# schematic-sac-xa-4s.net
KiCad netlist of a schematic drawn in Altium Designer
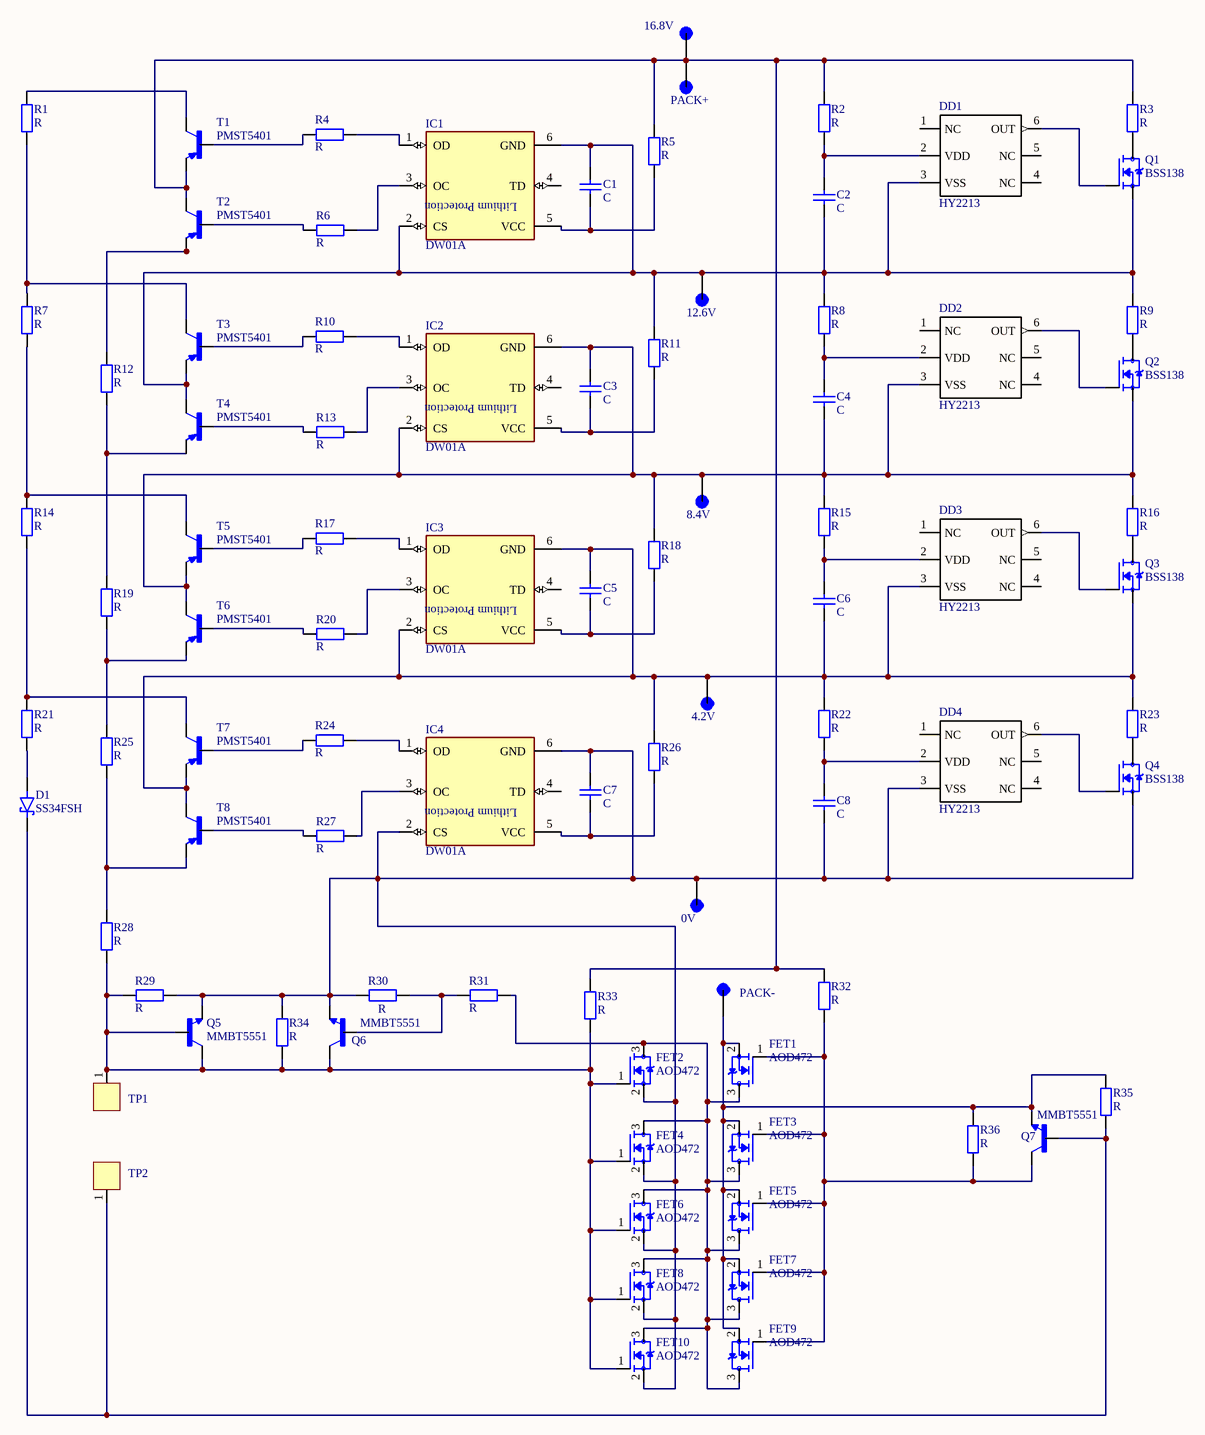
[diagram p0: schematic-sac-xa-4s.schdoc]

(export (version "E")
  (design (tool "Eeschema 10.0.6"))
  (components
    (comp (ref "0V")
      (value "5003")
      (footprint "KEYSTONE_5003")
      (fields (field (name "MF") "{'manufacturer': u'Keystone Electronics'}"))
      (libsource (lib "test pond") (part "5003"))
    )
    (comp (ref "4.2V")
      (value "5003")
      (footprint "KEYSTONE_5003")
      (fields (field (name "MF") "{'manufacturer': u'Keystone Electronics'}"))
      (libsource (lib "test pond") (part "5003"))
    )
    (comp (ref "8.4V")
      (value "5003")
      (footprint "KEYSTONE_5003")
      (fields (field (name "MF") "{'manufacturer': u'Keystone Electronics'}"))
      (libsource (lib "test pond") (part "5003"))
    )
    (comp (ref "12.6V")
      (value "5003")
      (footprint "KEYSTONE_5003")
      (fields (field (name "MF") "{'manufacturer': u'Keystone Electronics'}"))
      (libsource (lib "test pond") (part "5003"))
    )
    (comp (ref "16.8V")
      (value "5003")
      (footprint "KEYSTONE_5003")
      (fields (field (name "MF") "{'manufacturer': u'Keystone Electronics'}"))
      (libsource (lib "test pond") (part "5003"))
    )
    (comp (ref "C1")
      (value "C")
      (footprint "tu 0603")
      (description "Dán")
      (libsource (lib "Altium_Lib_by_KhueNguyenCreator") (part "Tu 0603 105 50V 10%"))
    )
    (comp (ref "C2")
      (value "C")
      (footprint "tu 0603")
      (description "Dán")
      (libsource (lib "Altium_Lib_by_KhueNguyenCreator") (part "Tu 0603 105 50V 10%"))
    )
    (comp (ref "C3")
      (value "C")
      (footprint "tu 0603")
      (description "Dán")
      (libsource (lib "Altium_Lib_by_KhueNguyenCreator") (part "Tu 0603 105 50V 10%"))
    )
    (comp (ref "C4")
      (value "C")
      (footprint "tu 0603")
      (description "Dán")
      (libsource (lib "Altium_Lib_by_KhueNguyenCreator") (part "Tu 0603 105 50V 10%"))
    )
    (comp (ref "C5")
      (value "C")
      (footprint "tu 0603")
      (description "Dán")
      (libsource (lib "Altium_Lib_by_KhueNguyenCreator") (part "Tu 0603 105 50V 10%"))
    )
    (comp (ref "C6")
      (value "C")
      (footprint "tu 0603")
      (description "Dán")
      (libsource (lib "Altium_Lib_by_KhueNguyenCreator") (part "Tu 0603 105 50V 10%"))
    )
    (comp (ref "C7")
      (value "C")
      (footprint "tu 0603")
      (description "Dán")
      (libsource (lib "Altium_Lib_by_KhueNguyenCreator") (part "Tu 0603 105 50V 10%"))
    )
    (comp (ref "C8")
      (value "C")
      (footprint "tu 0603")
      (description "Dán")
      (libsource (lib "Altium_Lib_by_KhueNguyenCreator") (part "Tu 0603 105 50V 10%"))
    )
    (comp (ref "D1")
      (value "SS34FSH")
      (footprint "SODFL4725X110N")
      (description "3A, 40V, Schottky Rectifier")
      (fields (field (name "MF") "Taiwan Semiconductor"))
      (libsource (lib "SS34FSH") (part "SS34FSH"))
    )
    (comp (ref "DD1")
      (value "HY2213")
      (footprint "SOT23-6")
      (description "1 Cell Li-ion/Polymer Battery Charge Balance IC")
      (libsource (lib "HY2213-BB3A") (part "HY2213"))
    )
    (comp (ref "DD2")
      (value "HY2213")
      (footprint "SOT23-6")
      (description "1 Cell Li-ion/Polymer Battery Charge Balance IC")
      (libsource (lib "HY2213-BB3A") (part "HY2213"))
    )
    (comp (ref "DD3")
      (value "HY2213")
      (footprint "SOT23-6")
      (description "1 Cell Li-ion/Polymer Battery Charge Balance IC")
      (libsource (lib "HY2213-BB3A") (part "HY2213"))
    )
    (comp (ref "DD4")
      (value "HY2213")
      (footprint "SOT23-6")
      (description "1 Cell Li-ion/Polymer Battery Charge Balance IC")
      (libsource (lib "HY2213-BB3A") (part "HY2213"))
    )
    (comp (ref "FET1")
      (value "AOD472")
      (footprint "PCBComponent_1")
      (libsource (lib "Mosfet AOD472") (part "AOD472"))
    )
    (comp (ref "FET2")
      (value "AOD472")
      (footprint "PCBComponent_1")
      (libsource (lib "Mosfet AOD472") (part "AOD472"))
    )
    (comp (ref "FET3")
      (value "AOD472")
      (footprint "PCBComponent_1")
      (libsource (lib "Mosfet AOD472") (part "AOD472"))
    )
    (comp (ref "FET4")
      (value "AOD472")
      (footprint "PCBComponent_1")
      (libsource (lib "Mosfet AOD472") (part "AOD472"))
    )
    (comp (ref "FET5")
      (value "AOD472")
      (footprint "PCBComponent_1")
      (libsource (lib "Mosfet AOD472") (part "AOD472"))
    )
    (comp (ref "FET6")
      (value "AOD472")
      (footprint "PCBComponent_1")
      (libsource (lib "Mosfet AOD472") (part "AOD472"))
    )
    (comp (ref "FET7")
      (value "AOD472")
      (footprint "PCBComponent_1")
      (libsource (lib "Mosfet AOD472") (part "AOD472"))
    )
    (comp (ref "FET8")
      (value "AOD472")
      (footprint "PCBComponent_1")
      (libsource (lib "Mosfet AOD472") (part "AOD472"))
    )
    (comp (ref "FET9")
      (value "AOD472")
      (footprint "PCBComponent_1")
      (libsource (lib "Mosfet AOD472") (part "AOD472"))
    )
    (comp (ref "FET10")
      (value "AOD472")
      (footprint "PCBComponent_1")
      (libsource (lib "Mosfet AOD472") (part "AOD472"))
    )
    (comp (ref "IC1")
      (value "DW01A")
      (footprint "SOT23-6")
      (description "One Cell Lithium-ion/Polymer Battery Protection IC")
      (fields (field (name "MF") "Fortune Semiconductor"))
      (libsource (lib "DW01A") (part "DW01A"))
    )
    (comp (ref "IC2")
      (value "DW01A")
      (footprint "SOT23-6")
      (description "One Cell Lithium-ion/Polymer Battery Protection IC")
      (fields (field (name "MF") "Fortune Semiconductor"))
      (libsource (lib "DW01A") (part "DW01A"))
    )
    (comp (ref "IC3")
      (value "DW01A")
      (footprint "SOT23-6")
      (description "One Cell Lithium-ion/Polymer Battery Protection IC")
      (fields (field (name "MF") "Fortune Semiconductor"))
      (libsource (lib "DW01A") (part "DW01A"))
    )
    (comp (ref "IC4")
      (value "DW01A")
      (footprint "SOT23-6")
      (description "One Cell Lithium-ion/Polymer Battery Protection IC")
      (fields (field (name "MF") "Fortune Semiconductor"))
      (libsource (lib "DW01A") (part "DW01A"))
    )
    (comp (ref "PACK+")
      (value "5003")
      (footprint "KEYSTONE_5003")
      (fields (field (name "MF") "{'manufacturer': u'Keystone Electronics'}"))
      (libsource (lib "test pond") (part "5003"))
    )
    (comp (ref "PACK-")
      (value "5003")
      (footprint "KEYSTONE_5003")
      (fields (field (name "MF") "{'manufacturer': u'Keystone Electronics'}"))
      (libsource (lib "test pond") (part "5003"))
    )
    (comp (ref "Q1")
      (value "BSS138")
      (footprint "SOT95P240X111-3N")
      (description "N-Channel 50V 220mA (Ta) 360mW (Ta) Surface Mount SOT-23-3")
      (fields (field (name "MF") "ON Semiconductor"))
      (libsource (lib "BSS138") (part "BSS138"))
    )
    (comp (ref "Q2")
      (value "BSS138")
      (footprint "SOT95P240X111-3N")
      (description "N-Channel 50V 220mA (Ta) 360mW (Ta) Surface Mount SOT-23-3")
      (fields (field (name "MF") "ON Semiconductor"))
      (libsource (lib "BSS138") (part "BSS138"))
    )
    (comp (ref "Q3")
      (value "BSS138")
      (footprint "SOT95P240X111-3N")
      (description "N-Channel 50V 220mA (Ta) 360mW (Ta) Surface Mount SOT-23-3")
      (fields (field (name "MF") "ON Semiconductor"))
      (libsource (lib "BSS138") (part "BSS138"))
    )
    (comp (ref "Q4")
      (value "BSS138")
      (footprint "SOT95P240X111-3N")
      (description "N-Channel 50V 220mA (Ta) 360mW (Ta) Surface Mount SOT-23-3")
      (fields (field (name "MF") "ON Semiconductor"))
      (libsource (lib "BSS138") (part "BSS138"))
    )
    (comp (ref "Q5")
      (value "MMBT5551")
      (footprint "SOT23-3")
      (description "Bipolar _BJT_ Transistor NPN 160V 600mA 225mW Surface Mount SOT-23-3 _TO-236_")
      (fields (field (name "MF") "ON Semiconductor"))
      (libsource (lib "") (part "MMBT5551_1"))
    )
    (comp (ref "Q6")
      (value "MMBT5551")
      (footprint "SOT23-3")
      (description "Bipolar _BJT_ Transistor NPN 160V 600mA 225mW Surface Mount SOT-23-3 _TO-236_")
      (fields (field (name "MF") "ON Semiconductor"))
      (libsource (lib "MMBT5551") (part "MMBT5551"))
    )
    (comp (ref "Q7")
      (value "MMBT5551")
      (footprint "SOT23-3")
      (description "Bipolar _BJT_ Transistor NPN 160V 600mA 225mW Surface Mount SOT-23-3 _TO-236_")
      (fields (field (name "MF") "ON Semiconductor"))
      (libsource (lib "MMBT5551") (part "MMBT5551"))
    )
    (comp (ref "R1")
      (value "R")
      (footprint "tro smd 0603")
      (description "Dán")
      (libsource (lib "Altium_Lib_by_KhueNguyenCreator") (part "Tro 0603 5% 100R"))
    )
    (comp (ref "R2")
      (value "R")
      (footprint "tro smd 0603")
      (description "Dán")
      (libsource (lib "Altium_Lib_by_KhueNguyenCreator") (part "Tro 0603 5% 100R"))
    )
    (comp (ref "R3")
      (value "R")
      (footprint "tro smd 0603")
      (description "Dán")
      (libsource (lib "Altium_Lib_by_KhueNguyenCreator") (part "Tro 0603 5% 100R"))
    )
    (comp (ref "R4")
      (value "R")
      (footprint "tro smd 0603")
      (description "Dán")
      (libsource (lib "Altium_Lib_by_KhueNguyenCreator") (part "Tro 0603 5% 100R"))
    )
    (comp (ref "R5")
      (value "R")
      (footprint "tro smd 0603")
      (description "Dán")
      (libsource (lib "Altium_Lib_by_KhueNguyenCreator") (part "Tro 0603 5% 100R"))
    )
    (comp (ref "R6")
      (value "R")
      (footprint "tro smd 0603")
      (description "Dán")
      (libsource (lib "Altium_Lib_by_KhueNguyenCreator") (part "Tro 0603 5% 100R"))
    )
    (comp (ref "R7")
      (value "R")
      (footprint "tro smd 0603")
      (description "Dán")
      (libsource (lib "Altium_Lib_by_KhueNguyenCreator") (part "Tro 0603 5% 100R"))
    )
    (comp (ref "R8")
      (value "R")
      (footprint "tro smd 0603")
      (description "Dán")
      (libsource (lib "Altium_Lib_by_KhueNguyenCreator") (part "Tro 0603 5% 100R"))
    )
    (comp (ref "R9")
      (value "R")
      (footprint "tro smd 0603")
      (description "Dán")
      (libsource (lib "Altium_Lib_by_KhueNguyenCreator") (part "Tro 0603 5% 100R"))
    )
    (comp (ref "R10")
      (value "R")
      (footprint "tro smd 0603")
      (description "Dán")
      (libsource (lib "Altium_Lib_by_KhueNguyenCreator") (part "Tro 0603 5% 100R"))
    )
    (comp (ref "R11")
      (value "R")
      (footprint "tro smd 0603")
      (description "Dán")
      (libsource (lib "Altium_Lib_by_KhueNguyenCreator") (part "Tro 0603 5% 100R"))
    )
    (comp (ref "R12")
      (value "R")
      (footprint "tro smd 0603")
      (description "Dán")
      (libsource (lib "Altium_Lib_by_KhueNguyenCreator") (part "Tro 0603 5% 100R"))
    )
    (comp (ref "R13")
      (value "R")
      (footprint "tro smd 0603")
      (description "Dán")
      (libsource (lib "Altium_Lib_by_KhueNguyenCreator") (part "Tro 0603 5% 100R"))
    )
    (comp (ref "R14")
      (value "R")
      (footprint "tro smd 0603")
      (description "Dán")
      (libsource (lib "Altium_Lib_by_KhueNguyenCreator") (part "Tro 0603 5% 100R"))
    )
    (comp (ref "R15")
      (value "R")
      (footprint "tro smd 0603")
      (description "Dán")
      (libsource (lib "Altium_Lib_by_KhueNguyenCreator") (part "Tro 0603 5% 100R"))
    )
    (comp (ref "R16")
      (value "R")
      (footprint "tro smd 0603")
      (description "Dán")
      (libsource (lib "Altium_Lib_by_KhueNguyenCreator") (part "Tro 0603 5% 100R"))
    )
    (comp (ref "R17")
      (value "R")
      (footprint "tro smd 0603")
      (description "Dán")
      (libsource (lib "Altium_Lib_by_KhueNguyenCreator") (part "Tro 0603 5% 100R"))
    )
    (comp (ref "R18")
      (value "R")
      (footprint "tro smd 0603")
      (description "Dán")
      (libsource (lib "Altium_Lib_by_KhueNguyenCreator") (part "Tro 0603 5% 100R"))
    )
    (comp (ref "R19")
      (value "R")
      (footprint "tro smd 0603")
      (description "Dán")
      (libsource (lib "Altium_Lib_by_KhueNguyenCreator") (part "Tro 0603 5% 100R"))
    )
    (comp (ref "R20")
      (value "R")
      (footprint "tro smd 0603")
      (description "Dán")
      (libsource (lib "Altium_Lib_by_KhueNguyenCreator") (part "Tro 0603 5% 100R"))
    )
    (comp (ref "R21")
      (value "R")
      (footprint "tro smd 0603")
      (description "Dán")
      (libsource (lib "Altium_Lib_by_KhueNguyenCreator") (part "Tro 0603 5% 100R"))
    )
    (comp (ref "R22")
      (value "R")
      (footprint "tro smd 0603")
      (description "Dán")
      (libsource (lib "Altium_Lib_by_KhueNguyenCreator") (part "Tro 0603 5% 100R"))
    )
    (comp (ref "R23")
      (value "R")
      (footprint "tro smd 0603")
      (description "Dán")
      (libsource (lib "Altium_Lib_by_KhueNguyenCreator") (part "Tro 0603 5% 100R"))
    )
    (comp (ref "R24")
      (value "R")
      (footprint "tro smd 0603")
      (description "Dán")
      (libsource (lib "Altium_Lib_by_KhueNguyenCreator") (part "Tro 0603 5% 100R"))
    )
    (comp (ref "R25")
      (value "R")
      (footprint "tro smd 0603")
      (description "Dán")
      (libsource (lib "Altium_Lib_by_KhueNguyenCreator") (part "Tro 0603 5% 100R"))
    )
    (comp (ref "R26")
      (value "R")
      (footprint "tro smd 0603")
      (description "Dán")
      (libsource (lib "Altium_Lib_by_KhueNguyenCreator") (part "Tro 0603 5% 100R"))
    )
    (comp (ref "R27")
      (value "R")
      (footprint "tro smd 0603")
      (description "Dán")
      (libsource (lib "Altium_Lib_by_KhueNguyenCreator") (part "Tro 0603 5% 100R"))
    )
    (comp (ref "R28")
      (value "R")
      (footprint "tro smd 0603")
      (description "Dán")
      (libsource (lib "Altium_Lib_by_KhueNguyenCreator") (part "Tro 0603 5% 100R"))
    )
    (comp (ref "R29")
      (value "R")
      (footprint "tro smd 0603")
      (description "Dán")
      (libsource (lib "Altium_Lib_by_KhueNguyenCreator") (part "Tro 0603 5% 100R"))
    )
    (comp (ref "R30")
      (value "R")
      (footprint "tro smd 0603")
      (description "Dán")
      (libsource (lib "Altium_Lib_by_KhueNguyenCreator") (part "Tro 0603 5% 100R"))
    )
    (comp (ref "R31")
      (value "R")
      (footprint "tro smd 0603")
      (description "Dán")
      (libsource (lib "Altium_Lib_by_KhueNguyenCreator") (part "Tro 0603 5% 100R"))
    )
    (comp (ref "R32")
      (value "R")
      (footprint "tro smd 0603")
      (description "Dán")
      (libsource (lib "Altium_Lib_by_KhueNguyenCreator") (part "Tro 0603 5% 100R"))
    )
    (comp (ref "R33")
      (value "R")
      (footprint "tro smd 0603")
      (description "Dán")
      (libsource (lib "Altium_Lib_by_KhueNguyenCreator") (part "Tro 0603 5% 100R"))
    )
    (comp (ref "R34")
      (value "R")
      (footprint "tro smd 0603")
      (description "Dán")
      (libsource (lib "Altium_Lib_by_KhueNguyenCreator") (part "Tro 0603 5% 100R"))
    )
    (comp (ref "R35")
      (value "R")
      (footprint "tro smd 0603")
      (description "Dán")
      (libsource (lib "Altium_Lib_by_KhueNguyenCreator") (part "Tro 0603 5% 100R"))
    )
    (comp (ref "R36")
      (value "R")
      (footprint "tro smd 0603")
      (description "Dán")
      (libsource (lib "Altium_Lib_by_KhueNguyenCreator") (part "Tro 0603 5% 100R"))
    )
    (comp (ref "T1")
      (value "PMST5401")
      (footprint "SOT323")
      (description "<p> <author>AAL Eindhoven MK</author><hr><p> <img src=\"http://www.nxp.com/img/NXP_logo.png\">")
      (libsource (lib "PMST5401") (part "PMST5401"))
    )
    (comp (ref "T2")
      (value "PMST5401")
      (footprint "SOT323")
      (description "<p> <author>AAL Eindhoven MK</author><hr><p> <img src=\"http://www.nxp.com/img/NXP_logo.png\">")
      (libsource (lib "PMST5401") (part "PMST5401"))
    )
    (comp (ref "T3")
      (value "PMST5401")
      (footprint "SOT323")
      (description "<p> <author>AAL Eindhoven MK</author><hr><p> <img src=\"http://www.nxp.com/img/NXP_logo.png\">")
      (libsource (lib "PMST5401") (part "PMST5401"))
    )
    (comp (ref "T4")
      (value "PMST5401")
      (footprint "SOT323")
      (description "<p> <author>AAL Eindhoven MK</author><hr><p> <img src=\"http://www.nxp.com/img/NXP_logo.png\">")
      (libsource (lib "PMST5401") (part "PMST5401"))
    )
    (comp (ref "T5")
      (value "PMST5401")
      (footprint "SOT323")
      (description "<p> <author>AAL Eindhoven MK</author><hr><p> <img src=\"http://www.nxp.com/img/NXP_logo.png\">")
      (libsource (lib "PMST5401") (part "PMST5401"))
    )
    (comp (ref "T6")
      (value "PMST5401")
      (footprint "SOT323")
      (description "<p> <author>AAL Eindhoven MK</author><hr><p> <img src=\"http://www.nxp.com/img/NXP_logo.png\">")
      (libsource (lib "PMST5401") (part "PMST5401"))
    )
    (comp (ref "T7")
      (value "PMST5401")
      (footprint "SOT323")
      (description "<p> <author>AAL Eindhoven MK</author><hr><p> <img src=\"http://www.nxp.com/img/NXP_logo.png\">")
      (libsource (lib "PMST5401") (part "PMST5401"))
    )
    (comp (ref "T8")
      (value "PMST5401")
      (footprint "SOT323")
      (description "<p> <author>AAL Eindhoven MK</author><hr><p> <img src=\"http://www.nxp.com/img/NXP_logo.png\">")
      (libsource (lib "PMST5401") (part "PMST5401"))
    )
    (comp (ref "TP1") (value "TP?") (footprint "TP") (libsource (lib "") (part "TP?_1")))
    (comp (ref "TP2") (value "TP?") (footprint "TP") (libsource (lib "Schlib1") (part "TP?")))
  )
  (nets
    (net (code "1") (name "Net-(D1-K)") (class "Default")
      (node (ref "D1") (pin "C") (pinfunction "K_C") (pintype "passive"))
      (node (ref "Q7") (pin "1") (pinfunction "B_1") (pintype "passive"))
      (node (ref "R35") (pin "2") (pinfunction "2_2") (pintype "passive"))
      (node (ref "TP2") (pin "1") (pinfunction "1_1") (pintype "passive"))
    )
    (net (code "2") (name "Net-(D1-PadA)") (class "Default")
      (node (ref "D1") (pin "A") (pinfunction "A_A") (pintype "passive"))
      (node (ref "R21") (pin "1") (pinfunction "1_1") (pintype "passive"))
    )
    (net (code "3") (name "Net-(DD1-OUT)") (class "Default")
      (node (ref "DD1") (pin "6") (pinfunction "OUT_6") (pintype "output"))
      (node (ref "Q1") (pin "1") (pinfunction "G_1") (pintype "passive"))
    )
    (net (code "4") (name "Net-(DD1-VDD)") (class "Default")
      (node (ref "C2") (pin "2") (pinfunction "2_2") (pintype "passive"))
      (node (ref "DD1") (pin "2") (pinfunction "VDD_2") (pintype "power_in"))
      (node (ref "R2") (pin "2") (pinfunction "2_2") (pintype "passive"))
    )
    (net (code "5") (name "Net-(DD1-VSS)") (class "Default")
      (node (ref "12.6V") (pin "TP") (pinfunction "TP_TP") (pintype "passive"))
      (node (ref "C1") (pin "2") (pinfunction "2_2") (pintype "passive"))
      (node (ref "C2") (pin "1") (pinfunction "1_1") (pintype "passive"))
      (node (ref "DD1") (pin "3") (pinfunction "VSS_3") (pintype "power_in"))
      (node (ref "IC1") (pin "2") (pinfunction "CS_2") (pintype "bidirectional"))
      (node (ref "IC1") (pin "6") (pinfunction "GND_6") (pintype "power_in"))
      (node (ref "Q1") (pin "2") (pinfunction "S_2") (pintype "passive"))
      (node (ref "R11") (pin "1") (pinfunction "1_1") (pintype "passive"))
      (node (ref "R8") (pin "1") (pinfunction "1_1") (pintype "passive"))
      (node (ref "R9") (pin "1") (pinfunction "1_1") (pintype "passive"))
      (node (ref "T3") (pin "2") (pinfunction "E_2") (pintype "passive"))
      (node (ref "T4") (pin "3") (pinfunction "C_3") (pintype "passive"))
    )
    (net (code "6") (name "Net-(DD2-OUT)") (class "Default")
      (node (ref "DD2") (pin "6") (pinfunction "OUT_6") (pintype "output"))
      (node (ref "Q2") (pin "1") (pinfunction "G_1") (pintype "passive"))
    )
    (net (code "7") (name "Net-(DD2-VDD)") (class "Default")
      (node (ref "C4") (pin "2") (pinfunction "2_2") (pintype "passive"))
      (node (ref "DD2") (pin "2") (pinfunction "VDD_2") (pintype "power_in"))
      (node (ref "R8") (pin "2") (pinfunction "2_2") (pintype "passive"))
    )
    (net (code "8") (name "Net-(DD2-VSS)") (class "Default")
      (node (ref "8.4V") (pin "TP") (pinfunction "TP_TP") (pintype "passive"))
      (node (ref "C3") (pin "2") (pinfunction "2_2") (pintype "passive"))
      (node (ref "C4") (pin "1") (pinfunction "1_1") (pintype "passive"))
      (node (ref "DD2") (pin "3") (pinfunction "VSS_3") (pintype "power_in"))
      (node (ref "IC2") (pin "2") (pinfunction "CS_2") (pintype "bidirectional"))
      (node (ref "IC2") (pin "6") (pinfunction "GND_6") (pintype "power_in"))
      (node (ref "Q2") (pin "2") (pinfunction "S_2") (pintype "passive"))
      (node (ref "R15") (pin "1") (pinfunction "1_1") (pintype "passive"))
      (node (ref "R16") (pin "1") (pinfunction "1_1") (pintype "passive"))
      (node (ref "R18") (pin "1") (pinfunction "1_1") (pintype "passive"))
      (node (ref "T5") (pin "2") (pinfunction "E_2") (pintype "passive"))
      (node (ref "T6") (pin "3") (pinfunction "C_3") (pintype "passive"))
    )
    (net (code "9") (name "Net-(DD3-OUT)") (class "Default")
      (node (ref "DD3") (pin "6") (pinfunction "OUT_6") (pintype "output"))
      (node (ref "Q3") (pin "1") (pinfunction "G_1") (pintype "passive"))
    )
    (net (code "10") (name "Net-(DD3-VDD)") (class "Default")
      (node (ref "C6") (pin "2") (pinfunction "2_2") (pintype "passive"))
      (node (ref "DD3") (pin "2") (pinfunction "VDD_2") (pintype "power_in"))
      (node (ref "R15") (pin "2") (pinfunction "2_2") (pintype "passive"))
    )
    (net (code "11") (name "Net-(DD3-VSS)") (class "Default")
      (node (ref "4.2V") (pin "TP") (pinfunction "TP_TP") (pintype "passive"))
      (node (ref "C5") (pin "2") (pinfunction "2_2") (pintype "passive"))
      (node (ref "C6") (pin "1") (pinfunction "1_1") (pintype "passive"))
      (node (ref "DD3") (pin "3") (pinfunction "VSS_3") (pintype "power_in"))
      (node (ref "IC3") (pin "2") (pinfunction "CS_2") (pintype "bidirectional"))
      (node (ref "IC3") (pin "6") (pinfunction "GND_6") (pintype "power_in"))
      (node (ref "Q3") (pin "2") (pinfunction "S_2") (pintype "passive"))
      (node (ref "R22") (pin "1") (pinfunction "1_1") (pintype "passive"))
      (node (ref "R23") (pin "1") (pinfunction "1_1") (pintype "passive"))
      (node (ref "R26") (pin "1") (pinfunction "1_1") (pintype "passive"))
      (node (ref "T7") (pin "2") (pinfunction "E_2") (pintype "passive"))
      (node (ref "T8") (pin "3") (pinfunction "C_3") (pintype "passive"))
    )
    (net (code "12") (name "Net-(DD4-OUT)") (class "Default")
      (node (ref "DD4") (pin "6") (pinfunction "OUT_6") (pintype "output"))
      (node (ref "Q4") (pin "1") (pinfunction "G_1") (pintype "passive"))
    )
    (net (code "13") (name "Net-(DD4-VDD)") (class "Default")
      (node (ref "C8") (pin "2") (pinfunction "2_2") (pintype "passive"))
      (node (ref "DD4") (pin "2") (pinfunction "VDD_2") (pintype "power_in"))
      (node (ref "R22") (pin "2") (pinfunction "2_2") (pintype "passive"))
    )
    (net (code "14") (name "Net-(DD4-VSS)") (class "Default")
      (node (ref "0V") (pin "TP") (pinfunction "TP_TP") (pintype "passive"))
      (node (ref "C7") (pin "2") (pinfunction "2_2") (pintype "passive"))
      (node (ref "C8") (pin "1") (pinfunction "1_1") (pintype "passive"))
      (node (ref "DD4") (pin "3") (pinfunction "VSS_3") (pintype "power_in"))
      (node (ref "FET10") (pin "2") (pinfunction "S_2") (pintype "passive"))
      (node (ref "FET2") (pin "2") (pinfunction "S_2") (pintype "passive"))
      (node (ref "FET4") (pin "2") (pinfunction "S_2") (pintype "passive"))
      (node (ref "FET6") (pin "2") (pinfunction "S_2") (pintype "passive"))
      (node (ref "FET8") (pin "2") (pinfunction "S_2") (pintype "passive"))
      (node (ref "IC4") (pin "2") (pinfunction "CS_2") (pintype "bidirectional"))
      (node (ref "IC4") (pin "6") (pinfunction "GND_6") (pintype "power_in"))
      (node (ref "Q4") (pin "2") (pinfunction "S_2") (pintype "passive"))
      (node (ref "Q5") (pin "2") (pinfunction "E_2") (pintype "passive"))
      (node (ref "Q6") (pin "2") (pinfunction "E_2") (pintype "passive"))
      (node (ref "R29") (pin "1") (pinfunction "1_1") (pintype "passive"))
      (node (ref "R30") (pin "2") (pinfunction "2_2") (pintype "passive"))
      (node (ref "R34") (pin "2") (pinfunction "2_2") (pintype "passive"))
    )
    (net (code "15") (name "Net-(FET1-D)") (class "Default")
      (node (ref "FET1") (pin "3") (pinfunction "D_3") (pintype "passive"))
      (node (ref "FET10") (pin "3") (pinfunction "D_3") (pintype "passive"))
      (node (ref "FET2") (pin "3") (pinfunction "D_3") (pintype "passive"))
      (node (ref "FET3") (pin "3") (pinfunction "D_3") (pintype "passive"))
      (node (ref "FET4") (pin "3") (pinfunction "D_3") (pintype "passive"))
      (node (ref "FET5") (pin "3") (pinfunction "D_3") (pintype "passive"))
      (node (ref "FET6") (pin "3") (pinfunction "D_3") (pintype "passive"))
      (node (ref "FET7") (pin "3") (pinfunction "D_3") (pintype "passive"))
      (node (ref "FET8") (pin "3") (pinfunction "D_3") (pintype "passive"))
      (node (ref "FET9") (pin "3") (pinfunction "D_3") (pintype "passive"))
      (node (ref "R31") (pin "1") (pinfunction "1_1") (pintype "passive"))
    )
    (net (code "16") (name "Net-(FET1-G)") (class "Default")
      (node (ref "FET1") (pin "1") (pinfunction "G_1") (pintype "passive"))
      (node (ref "FET3") (pin "1") (pinfunction "G_1") (pintype "passive"))
      (node (ref "FET5") (pin "1") (pinfunction "G_1") (pintype "passive"))
      (node (ref "FET7") (pin "1") (pinfunction "G_1") (pintype "passive"))
      (node (ref "FET9") (pin "1") (pinfunction "G_1") (pintype "passive"))
      (node (ref "Q7") (pin "3") (pinfunction "C_3") (pintype "passive"))
      (node (ref "R32") (pin "2") (pinfunction "2_2") (pintype "passive"))
      (node (ref "R36") (pin "2") (pinfunction "2_2") (pintype "passive"))
    )
    (net (code "17") (name "Net-(FET1-S)") (class "Default")
      (node (ref "FET1") (pin "2") (pinfunction "S_2") (pintype "passive"))
      (node (ref "FET3") (pin "2") (pinfunction "S_2") (pintype "passive"))
      (node (ref "FET5") (pin "2") (pinfunction "S_2") (pintype "passive"))
      (node (ref "FET7") (pin "2") (pinfunction "S_2") (pintype "passive"))
      (node (ref "FET9") (pin "2") (pinfunction "S_2") (pintype "passive"))
      (node (ref "PACK-") (pin "TP") (pinfunction "TP_TP") (pintype "passive"))
      (node (ref "Q7") (pin "2") (pinfunction "E_2") (pintype "passive"))
      (node (ref "R35") (pin "1") (pinfunction "1_1") (pintype "passive"))
      (node (ref "R36") (pin "1") (pinfunction "1_1") (pintype "passive"))
    )
    (net (code "18") (name "Net-(FET10-G)") (class "Default")
      (node (ref "FET10") (pin "1") (pinfunction "G_1") (pintype "passive"))
      (node (ref "FET2") (pin "1") (pinfunction "G_1") (pintype "passive"))
      (node (ref "FET4") (pin "1") (pinfunction "G_1") (pintype "passive"))
      (node (ref "FET6") (pin "1") (pinfunction "G_1") (pintype "passive"))
      (node (ref "FET8") (pin "1") (pinfunction "G_1") (pintype "passive"))
      (node (ref "Q5") (pin "1") (pinfunction "B_1") (pintype "passive"))
      (node (ref "Q5") (pin "3") (pinfunction "C_3") (pintype "passive"))
      (node (ref "Q6") (pin "3") (pinfunction "C_3") (pintype "passive"))
      (node (ref "R28") (pin "1") (pinfunction "1_1") (pintype "passive"))
      (node (ref "R29") (pin "2") (pinfunction "2_2") (pintype "passive"))
      (node (ref "R33") (pin "2") (pinfunction "2_2") (pintype "passive"))
      (node (ref "R34") (pin "1") (pinfunction "1_1") (pintype "passive"))
      (node (ref "TP1") (pin "1") (pinfunction "1_1") (pintype "passive"))
    )
    (net (code "19") (name "Net-(IC1-OC)") (class "Default")
      (node (ref "IC1") (pin "3") (pinfunction "OC_3") (pintype "bidirectional"))
      (node (ref "R6") (pin "1") (pinfunction "1_1") (pintype "passive"))
    )
    (net (code "20") (name "Net-(IC1-OD)") (class "Default")
      (node (ref "IC1") (pin "1") (pinfunction "OD_1") (pintype "bidirectional"))
      (node (ref "R4") (pin "1") (pinfunction "1_1") (pintype "passive"))
    )
    (net (code "21") (name "Net-(IC1-VCC)") (class "Default")
      (node (ref "C1") (pin "1") (pinfunction "1_1") (pintype "passive"))
      (node (ref "IC1") (pin "5") (pinfunction "VCC_5") (pintype "power_in"))
      (node (ref "R5") (pin "2") (pinfunction "2_2") (pintype "passive"))
    )
    (net (code "22") (name "Net-(IC2-OC)") (class "Default")
      (node (ref "IC2") (pin "3") (pinfunction "OC_3") (pintype "bidirectional"))
      (node (ref "R13") (pin "1") (pinfunction "1_1") (pintype "passive"))
    )
    (net (code "23") (name "Net-(IC2-OD)") (class "Default")
      (node (ref "IC2") (pin "1") (pinfunction "OD_1") (pintype "bidirectional"))
      (node (ref "R10") (pin "1") (pinfunction "1_1") (pintype "passive"))
    )
    (net (code "24") (name "Net-(IC2-VCC)") (class "Default")
      (node (ref "C3") (pin "1") (pinfunction "1_1") (pintype "passive"))
      (node (ref "IC2") (pin "5") (pinfunction "VCC_5") (pintype "power_in"))
      (node (ref "R11") (pin "2") (pinfunction "2_2") (pintype "passive"))
    )
    (net (code "25") (name "Net-(IC3-OC)") (class "Default")
      (node (ref "IC3") (pin "3") (pinfunction "OC_3") (pintype "bidirectional"))
      (node (ref "R20") (pin "1") (pinfunction "1_1") (pintype "passive"))
    )
    (net (code "26") (name "Net-(IC3-OD)") (class "Default")
      (node (ref "IC3") (pin "1") (pinfunction "OD_1") (pintype "bidirectional"))
      (node (ref "R17") (pin "1") (pinfunction "1_1") (pintype "passive"))
    )
    (net (code "27") (name "Net-(IC3-VCC)") (class "Default")
      (node (ref "C5") (pin "1") (pinfunction "1_1") (pintype "passive"))
      (node (ref "IC3") (pin "5") (pinfunction "VCC_5") (pintype "power_in"))
      (node (ref "R18") (pin "2") (pinfunction "2_2") (pintype "passive"))
    )
    (net (code "28") (name "Net-(IC4-OC)") (class "Default")
      (node (ref "IC4") (pin "3") (pinfunction "OC_3") (pintype "bidirectional"))
      (node (ref "R27") (pin "1") (pinfunction "1_1") (pintype "passive"))
    )
    (net (code "29") (name "Net-(IC4-OD)") (class "Default")
      (node (ref "IC4") (pin "1") (pinfunction "OD_1") (pintype "bidirectional"))
      (node (ref "R24") (pin "1") (pinfunction "1_1") (pintype "passive"))
    )
    (net (code "30") (name "Net-(IC4-VCC)") (class "Default")
      (node (ref "C7") (pin "1") (pinfunction "1_1") (pintype "passive"))
      (node (ref "IC4") (pin "5") (pinfunction "VCC_5") (pintype "power_in"))
      (node (ref "R26") (pin "2") (pinfunction "2_2") (pintype "passive"))
    )
    (net (code "31") (name "Net-(Q1-D)") (class "Default")
      (node (ref "Q1") (pin "3") (pinfunction "D_3") (pintype "passive"))
      (node (ref "R3") (pin "2") (pinfunction "2_2") (pintype "passive"))
    )
    (net (code "32") (name "Net-(Q2-D)") (class "Default")
      (node (ref "Q2") (pin "3") (pinfunction "D_3") (pintype "passive"))
      (node (ref "R9") (pin "2") (pinfunction "2_2") (pintype "passive"))
    )
    (net (code "33") (name "Net-(Q3-D)") (class "Default")
      (node (ref "Q3") (pin "3") (pinfunction "D_3") (pintype "passive"))
      (node (ref "R16") (pin "2") (pinfunction "2_2") (pintype "passive"))
    )
    (net (code "34") (name "Net-(Q4-D)") (class "Default")
      (node (ref "Q4") (pin "3") (pinfunction "D_3") (pintype "passive"))
      (node (ref "R23") (pin "2") (pinfunction "2_2") (pintype "passive"))
    )
    (net (code "35") (name "Net-(Q6-B)") (class "Default")
      (node (ref "Q6") (pin "1") (pinfunction "B_1") (pintype "passive"))
      (node (ref "R30") (pin "1") (pinfunction "1_1") (pintype "passive"))
      (node (ref "R31") (pin "2") (pinfunction "2_2") (pintype "passive"))
    )
    (net (code "36") (name "Net-(T1-B)") (class "Default")
      (node (ref "R4") (pin "2") (pinfunction "2_2") (pintype "passive"))
      (node (ref "T1") (pin "1") (pinfunction "B_1") (pintype "passive"))
    )
    (net (code "37") (name "Net-(T1-C)") (class "Default")
      (node (ref "R1") (pin "2") (pinfunction "2_2") (pintype "passive"))
      (node (ref "T1") (pin "3") (pinfunction "C_3") (pintype "passive"))
    )
    (net (code "38") (name "Net-(T1-E)") (class "Default")
      (node (ref "16.8V") (pin "TP") (pinfunction "TP_TP") (pintype "passive"))
      (node (ref "PACK+") (pin "TP") (pinfunction "TP_TP") (pintype "passive"))
      (node (ref "R2") (pin "1") (pinfunction "1_1") (pintype "passive"))
      (node (ref "R3") (pin "1") (pinfunction "1_1") (pintype "passive"))
      (node (ref "R32") (pin "1") (pinfunction "1_1") (pintype "passive"))
      (node (ref "R33") (pin "1") (pinfunction "1_1") (pintype "passive"))
      (node (ref "R5") (pin "1") (pinfunction "1_1") (pintype "passive"))
      (node (ref "T1") (pin "2") (pinfunction "E_2") (pintype "passive"))
      (node (ref "T2") (pin "3") (pinfunction "C_3") (pintype "passive"))
    )
    (net (code "39") (name "Net-(T2-B)") (class "Default")
      (node (ref "R6") (pin "2") (pinfunction "2_2") (pintype "passive"))
      (node (ref "T2") (pin "1") (pinfunction "B_1") (pintype "passive"))
    )
    (net (code "40") (name "Net-(T2-E)") (class "Default")
      (node (ref "R12") (pin "2") (pinfunction "2_2") (pintype "passive"))
      (node (ref "T2") (pin "2") (pinfunction "E_2") (pintype "passive"))
    )
    (net (code "41") (name "Net-(T3-B)") (class "Default")
      (node (ref "R10") (pin "2") (pinfunction "2_2") (pintype "passive"))
      (node (ref "T3") (pin "1") (pinfunction "B_1") (pintype "passive"))
    )
    (net (code "42") (name "Net-(T3-C)") (class "Default")
      (node (ref "R1") (pin "1") (pinfunction "1_1") (pintype "passive"))
      (node (ref "R7") (pin "2") (pinfunction "2_2") (pintype "passive"))
      (node (ref "T3") (pin "3") (pinfunction "C_3") (pintype "passive"))
    )
    (net (code "43") (name "Net-(T4-B)") (class "Default")
      (node (ref "R13") (pin "2") (pinfunction "2_2") (pintype "passive"))
      (node (ref "T4") (pin "1") (pinfunction "B_1") (pintype "passive"))
    )
    (net (code "44") (name "Net-(T4-E)") (class "Default")
      (node (ref "R12") (pin "1") (pinfunction "1_1") (pintype "passive"))
      (node (ref "R19") (pin "2") (pinfunction "2_2") (pintype "passive"))
      (node (ref "T4") (pin "2") (pinfunction "E_2") (pintype "passive"))
    )
    (net (code "45") (name "Net-(T5-B)") (class "Default")
      (node (ref "R17") (pin "2") (pinfunction "2_2") (pintype "passive"))
      (node (ref "T5") (pin "1") (pinfunction "B_1") (pintype "passive"))
    )
    (net (code "46") (name "Net-(T5-C)") (class "Default")
      (node (ref "R14") (pin "2") (pinfunction "2_2") (pintype "passive"))
      (node (ref "R7") (pin "1") (pinfunction "1_1") (pintype "passive"))
      (node (ref "T5") (pin "3") (pinfunction "C_3") (pintype "passive"))
    )
    (net (code "47") (name "Net-(T6-B)") (class "Default")
      (node (ref "R20") (pin "2") (pinfunction "2_2") (pintype "passive"))
      (node (ref "T6") (pin "1") (pinfunction "B_1") (pintype "passive"))
    )
    (net (code "48") (name "Net-(T6-E)") (class "Default")
      (node (ref "R19") (pin "1") (pinfunction "1_1") (pintype "passive"))
      (node (ref "R25") (pin "2") (pinfunction "2_2") (pintype "passive"))
      (node (ref "T6") (pin "2") (pinfunction "E_2") (pintype "passive"))
    )
    (net (code "49") (name "Net-(T7-B)") (class "Default")
      (node (ref "R24") (pin "2") (pinfunction "2_2") (pintype "passive"))
      (node (ref "T7") (pin "1") (pinfunction "B_1") (pintype "passive"))
    )
    (net (code "50") (name "Net-(T7-C)") (class "Default")
      (node (ref "R14") (pin "1") (pinfunction "1_1") (pintype "passive"))
      (node (ref "R21") (pin "2") (pinfunction "2_2") (pintype "passive"))
      (node (ref "T7") (pin "3") (pinfunction "C_3") (pintype "passive"))
    )
    (net (code "51") (name "Net-(T8-B)") (class "Default")
      (node (ref "R27") (pin "2") (pinfunction "2_2") (pintype "passive"))
      (node (ref "T8") (pin "1") (pinfunction "B_1") (pintype "passive"))
    )
    (net (code "52") (name "Net-(T8-E)") (class "Default")
      (node (ref "R25") (pin "1") (pinfunction "1_1") (pintype "passive"))
      (node (ref "R28") (pin "2") (pinfunction "2_2") (pintype "passive"))
      (node (ref "T8") (pin "2") (pinfunction "E_2") (pintype "passive"))
    )
    (net (code "53") (name "unconnected-(DD1-NC-Pad1)") (class "Default")
      (node (ref "DD1") (pin "1") (pinfunction "NC_1") (pintype "tri_state"))
    )
    (net (code "54") (name "unconnected-(DD1-NC-Pad4)") (class "Default")
      (node (ref "DD1") (pin "4") (pinfunction "NC_4") (pintype "tri_state"))
    )
    (net (code "55") (name "unconnected-(DD1-NC-Pad5)") (class "Default")
      (node (ref "DD1") (pin "5") (pinfunction "NC_5") (pintype "tri_state"))
    )
    (net (code "56") (name "unconnected-(DD2-NC-Pad1)") (class "Default")
      (node (ref "DD2") (pin "1") (pinfunction "NC_1") (pintype "tri_state"))
    )
    (net (code "57") (name "unconnected-(DD2-NC-Pad4)") (class "Default")
      (node (ref "DD2") (pin "4") (pinfunction "NC_4") (pintype "tri_state"))
    )
    (net (code "58") (name "unconnected-(DD2-NC-Pad5)") (class "Default")
      (node (ref "DD2") (pin "5") (pinfunction "NC_5") (pintype "tri_state"))
    )
    (net (code "59") (name "unconnected-(DD3-NC-Pad1)") (class "Default")
      (node (ref "DD3") (pin "1") (pinfunction "NC_1") (pintype "tri_state"))
    )
    (net (code "60") (name "unconnected-(DD3-NC-Pad4)") (class "Default")
      (node (ref "DD3") (pin "4") (pinfunction "NC_4") (pintype "tri_state"))
    )
    (net (code "61") (name "unconnected-(DD3-NC-Pad5)") (class "Default")
      (node (ref "DD3") (pin "5") (pinfunction "NC_5") (pintype "tri_state"))
    )
    (net (code "62") (name "unconnected-(DD4-NC-Pad1)") (class "Default")
      (node (ref "DD4") (pin "1") (pinfunction "NC_1") (pintype "tri_state"))
    )
    (net (code "63") (name "unconnected-(DD4-NC-Pad4)") (class "Default")
      (node (ref "DD4") (pin "4") (pinfunction "NC_4") (pintype "tri_state"))
    )
    (net (code "64") (name "unconnected-(DD4-NC-Pad5)") (class "Default")
      (node (ref "DD4") (pin "5") (pinfunction "NC_5") (pintype "tri_state"))
    )
    (net (code "65") (name "unconnected-(IC1-TD-Pad4)") (class "Default")
      (node (ref "IC1") (pin "4") (pinfunction "TD_4") (pintype "bidirectional"))
    )
    (net (code "66") (name "unconnected-(IC2-TD-Pad4)") (class "Default")
      (node (ref "IC2") (pin "4") (pinfunction "TD_4") (pintype "bidirectional"))
    )
    (net (code "67") (name "unconnected-(IC3-TD-Pad4)") (class "Default")
      (node (ref "IC3") (pin "4") (pinfunction "TD_4") (pintype "bidirectional"))
    )
    (net (code "68") (name "unconnected-(IC4-TD-Pad4)") (class "Default")
      (node (ref "IC4") (pin "4") (pinfunction "TD_4") (pintype "bidirectional"))
    )
  )
)
